# 4X_22_GND_Pin_Connector.net
KiCad netlist of a schematic drawn in Altium Designer
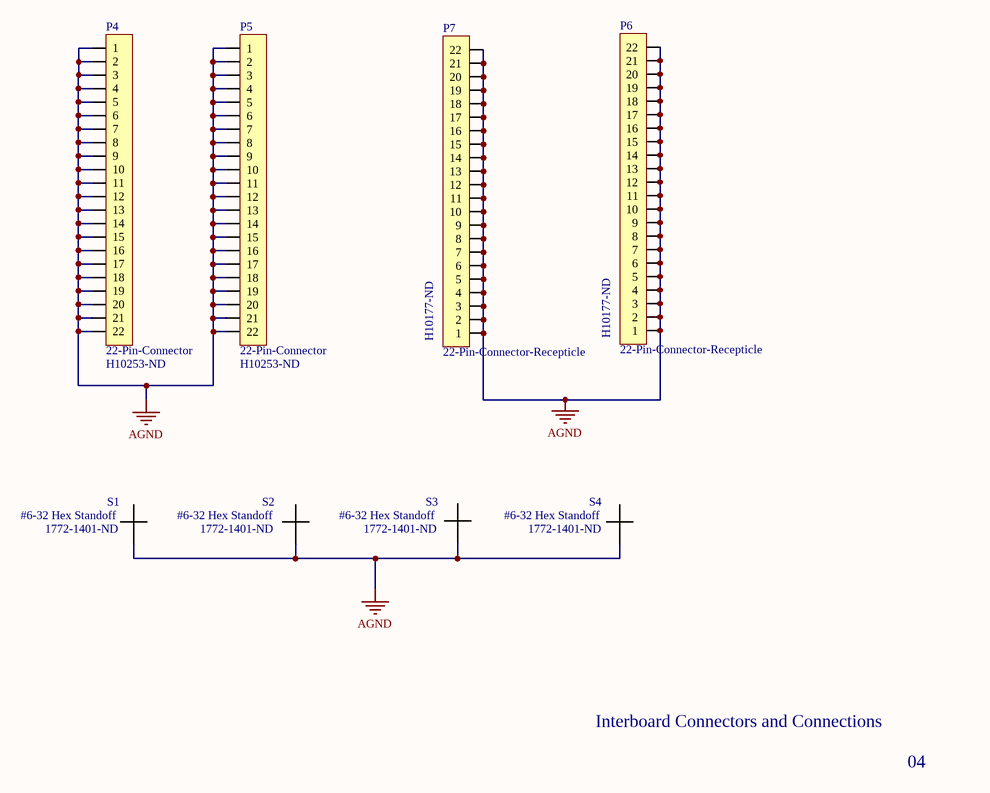
[diagram p0: 4X_22_GND_Pin_Connector.SchDoc]

(export (version "E")
  (design (tool "Eeschema 10.0.6"))
  (components
    (comp (ref "P4")
      (value "22-Pin-Connector")
      (footprint "22-Pin Conenctor")
      (description "Current Therm Connector")
      (fields
        (field (name "MANUFACTURER") "Hirose")
        (field (name "MANUFACTURER PART NUMBER") "DF11-22DP-2DS(24)")
        (field (name "SUPPLIER PART NUMBER 1") "H10253-ND")
      )
      (libsource (lib "Schematic_Library") (part "22-Pin-Connector"))
    )
    (comp (ref "P5")
      (value "22-Pin-Connector")
      (footprint "22-Pin Conenctor")
      (description "Current Therm Connector")
      (fields
        (field (name "MANUFACTURER") "Hirose")
        (field (name "MANUFACTURER PART NUMBER") "DF11-22DP-2DS(24)")
        (field (name "SUPPLIER PART NUMBER 1") "H10253-ND")
      )
      (libsource (lib "Schematic_Library") (part "22-Pin-Connector"))
    )
    (comp (ref "P6")
      (value "22-Pin-Connector-Recepticle")
      (footprint "22 POS Connector Recepticle")
      (fields
        (field (name "MANUFACTURER") "Hirose")
        (field (name "MANUFACTURER PART NUMBER") "DF11-22DS-2DSA(05)")
        (field (name "SUPPLIER PART NUMBER 1") "H10177-ND")
      )
      (libsource (lib "Schematic_Library") (part "22-Pin-Connector-Recepticle"))
    )
    (comp (ref "P7")
      (value "22-Pin-Connector-Recepticle")
      (footprint "22 POS Connector Recepticle")
      (fields
        (field (name "MANUFACTURER") "Hirose")
        (field (name "MANUFACTURER PART NUMBER") "DF11-22DS-2DSA(05)")
        (field (name "SUPPLIER PART NUMBER 1") "H10177-ND")
      )
      (libsource (lib "Schematic_Library") (part "22-Pin-Connector-Recepticle"))
    )
    (comp (ref "S1")
      (value "#6-32 Hex Standoff")
      (footprint "#6-32 GND Standoff")
      (description "Hex standoff for Thermistor GND Board")
      (fields
        (field (name "MANUFACTURER") "RAF")
        (field (name "MANUFACTURER PART NUMBER") "2104-632-AL")
        (field (name "SUPPLIER PART NUMBER 1") "1772-1401-ND")
      )
      (libsource (lib "Schematic_Library") (part "#6-32 Hex Standoff"))
    )
    (comp (ref "S2")
      (value "#6-32 Hex Standoff")
      (footprint "#6-32 GND Standoff")
      (description "Hex standoff for Thermistor GND Board")
      (fields
        (field (name "MANUFACTURER") "RAF")
        (field (name "MANUFACTURER PART NUMBER") "2104-632-AL")
        (field (name "SUPPLIER PART NUMBER 1") "1772-1401-ND")
      )
      (libsource (lib "Schematic_Library") (part "#6-32 Hex Standoff"))
    )
    (comp (ref "S3")
      (value "#6-32 Hex Standoff")
      (footprint "#6-32 GND Standoff")
      (description "Hex standoff for Thermistor GND Board")
      (fields
        (field (name "MANUFACTURER") "RAF")
        (field (name "MANUFACTURER PART NUMBER") "2104-632-AL")
        (field (name "SUPPLIER PART NUMBER 1") "1772-1401-ND")
      )
      (libsource (lib "Schematic_Library") (part "#6-32 Hex Standoff"))
    )
    (comp (ref "S4")
      (value "#6-32 Hex Standoff")
      (footprint "#6-32 GND Standoff")
      (description "Hex standoff for Thermistor GND Board")
      (fields
        (field (name "MANUFACTURER") "RAF")
        (field (name "MANUFACTURER PART NUMBER") "2104-632-AL")
        (field (name "SUPPLIER PART NUMBER 1") "1772-1401-ND")
      )
      (libsource (lib "Schematic_Library") (part "#6-32 Hex Standoff"))
    )
  )
  (nets
    (net (code "1") (name "AGND") (class "Default")
      (node (ref "P4") (pin "1") (pinfunction "1_1") (pintype "passive"))
      (node (ref "P4") (pin "10") (pinfunction "10_10") (pintype "passive"))
      (node (ref "P4") (pin "11") (pinfunction "11_11") (pintype "passive"))
      (node (ref "P4") (pin "12") (pinfunction "12_12") (pintype "passive"))
      (node (ref "P4") (pin "13") (pinfunction "13_13") (pintype "passive"))
      (node (ref "P4") (pin "14") (pinfunction "14_14") (pintype "passive"))
      (node (ref "P4") (pin "15") (pinfunction "15_15") (pintype "passive"))
      (node (ref "P4") (pin "16") (pinfunction "16_16") (pintype "passive"))
      (node (ref "P4") (pin "17") (pinfunction "17_17") (pintype "passive"))
      (node (ref "P4") (pin "18") (pinfunction "18_18") (pintype "passive"))
      (node (ref "P4") (pin "19") (pinfunction "19_19") (pintype "passive"))
      (node (ref "P4") (pin "2") (pinfunction "2_2") (pintype "passive"))
      (node (ref "P4") (pin "20") (pinfunction "20_20") (pintype "passive"))
      (node (ref "P4") (pin "21") (pinfunction "21_21") (pintype "passive"))
      (node (ref "P4") (pin "22") (pinfunction "22_22") (pintype "passive"))
      (node (ref "P4") (pin "3") (pinfunction "3_3") (pintype "passive"))
      (node (ref "P4") (pin "4") (pinfunction "4_4") (pintype "passive"))
      (node (ref "P4") (pin "5") (pinfunction "5_5") (pintype "passive"))
      (node (ref "P4") (pin "6") (pinfunction "6_6") (pintype "passive"))
      (node (ref "P4") (pin "7") (pinfunction "7_7") (pintype "passive"))
      (node (ref "P4") (pin "8") (pinfunction "8_8") (pintype "passive"))
      (node (ref "P4") (pin "9") (pinfunction "9_9") (pintype "passive"))
      (node (ref "P5") (pin "1") (pinfunction "1_1") (pintype "passive"))
      (node (ref "P5") (pin "10") (pinfunction "10_10") (pintype "passive"))
      (node (ref "P5") (pin "11") (pinfunction "11_11") (pintype "passive"))
      (node (ref "P5") (pin "12") (pinfunction "12_12") (pintype "passive"))
      (node (ref "P5") (pin "13") (pinfunction "13_13") (pintype "passive"))
      (node (ref "P5") (pin "14") (pinfunction "14_14") (pintype "passive"))
      (node (ref "P5") (pin "15") (pinfunction "15_15") (pintype "passive"))
      (node (ref "P5") (pin "16") (pinfunction "16_16") (pintype "passive"))
      (node (ref "P5") (pin "17") (pinfunction "17_17") (pintype "passive"))
      (node (ref "P5") (pin "18") (pinfunction "18_18") (pintype "passive"))
      (node (ref "P5") (pin "19") (pinfunction "19_19") (pintype "passive"))
      (node (ref "P5") (pin "2") (pinfunction "2_2") (pintype "passive"))
      (node (ref "P5") (pin "20") (pinfunction "20_20") (pintype "passive"))
      (node (ref "P5") (pin "21") (pinfunction "21_21") (pintype "passive"))
      (node (ref "P5") (pin "22") (pinfunction "22_22") (pintype "passive"))
      (node (ref "P5") (pin "3") (pinfunction "3_3") (pintype "passive"))
      (node (ref "P5") (pin "4") (pinfunction "4_4") (pintype "passive"))
      (node (ref "P5") (pin "5") (pinfunction "5_5") (pintype "passive"))
      (node (ref "P5") (pin "6") (pinfunction "6_6") (pintype "passive"))
      (node (ref "P5") (pin "7") (pinfunction "7_7") (pintype "passive"))
      (node (ref "P5") (pin "8") (pinfunction "8_8") (pintype "passive"))
      (node (ref "P5") (pin "9") (pinfunction "9_9") (pintype "passive"))
      (node (ref "P6") (pin "1") (pinfunction "1_1") (pintype "passive"))
      (node (ref "P6") (pin "10") (pinfunction "10_10") (pintype "passive"))
      (node (ref "P6") (pin "11") (pinfunction "11_11") (pintype "passive"))
      (node (ref "P6") (pin "12") (pinfunction "12_12") (pintype "passive"))
      (node (ref "P6") (pin "13") (pinfunction "13_13") (pintype "passive"))
      (node (ref "P6") (pin "14") (pinfunction "14_14") (pintype "passive"))
      (node (ref "P6") (pin "15") (pinfunction "15_15") (pintype "passive"))
      (node (ref "P6") (pin "16") (pinfunction "16_16") (pintype "passive"))
      (node (ref "P6") (pin "17") (pinfunction "17_17") (pintype "passive"))
      (node (ref "P6") (pin "18") (pinfunction "18_18") (pintype "passive"))
      (node (ref "P6") (pin "19") (pinfunction "19_19") (pintype "passive"))
      (node (ref "P6") (pin "2") (pinfunction "2_2") (pintype "passive"))
      (node (ref "P6") (pin "20") (pinfunction "20_20") (pintype "passive"))
      (node (ref "P6") (pin "21") (pinfunction "21_21") (pintype "passive"))
      (node (ref "P6") (pin "22") (pinfunction "22_22") (pintype "passive"))
      (node (ref "P6") (pin "3") (pinfunction "3_3") (pintype "passive"))
      (node (ref "P6") (pin "4") (pinfunction "4_4") (pintype "passive"))
      (node (ref "P6") (pin "5") (pinfunction "5_5") (pintype "passive"))
      (node (ref "P6") (pin "6") (pinfunction "6_6") (pintype "passive"))
      (node (ref "P6") (pin "7") (pinfunction "7_7") (pintype "passive"))
      (node (ref "P6") (pin "8") (pinfunction "8_8") (pintype "passive"))
      (node (ref "P6") (pin "9") (pinfunction "9_9") (pintype "passive"))
      (node (ref "P7") (pin "1") (pinfunction "1_1") (pintype "passive"))
      (node (ref "P7") (pin "10") (pinfunction "10_10") (pintype "passive"))
      (node (ref "P7") (pin "11") (pinfunction "11_11") (pintype "passive"))
      (node (ref "P7") (pin "12") (pinfunction "12_12") (pintype "passive"))
      (node (ref "P7") (pin "13") (pinfunction "13_13") (pintype "passive"))
      (node (ref "P7") (pin "14") (pinfunction "14_14") (pintype "passive"))
      (node (ref "P7") (pin "15") (pinfunction "15_15") (pintype "passive"))
      (node (ref "P7") (pin "16") (pinfunction "16_16") (pintype "passive"))
      (node (ref "P7") (pin "17") (pinfunction "17_17") (pintype "passive"))
      (node (ref "P7") (pin "18") (pinfunction "18_18") (pintype "passive"))
      (node (ref "P7") (pin "19") (pinfunction "19_19") (pintype "passive"))
      (node (ref "P7") (pin "2") (pinfunction "2_2") (pintype "passive"))
      (node (ref "P7") (pin "20") (pinfunction "20_20") (pintype "passive"))
      (node (ref "P7") (pin "21") (pinfunction "21_21") (pintype "passive"))
      (node (ref "P7") (pin "22") (pinfunction "22_22") (pintype "passive"))
      (node (ref "P7") (pin "3") (pinfunction "3_3") (pintype "passive"))
      (node (ref "P7") (pin "4") (pinfunction "4_4") (pintype "passive"))
      (node (ref "P7") (pin "5") (pinfunction "5_5") (pintype "passive"))
      (node (ref "P7") (pin "6") (pinfunction "6_6") (pintype "passive"))
      (node (ref "P7") (pin "7") (pinfunction "7_7") (pintype "passive"))
      (node (ref "P7") (pin "8") (pinfunction "8_8") (pintype "passive"))
      (node (ref "P7") (pin "9") (pinfunction "9_9") (pintype "passive"))
      (node (ref "S1") (pin "1") (pinfunction "1_1") (pintype "passive"))
      (node (ref "S2") (pin "1") (pinfunction "1_1") (pintype "passive"))
      (node (ref "S3") (pin "1") (pinfunction "1_1") (pintype "passive"))
      (node (ref "S4") (pin "1") (pinfunction "1_1") (pintype "passive"))
    )
  )
)
